# SCH_tactile_cube.net
KiCad netlist of a schematic drawn in EasyEDA
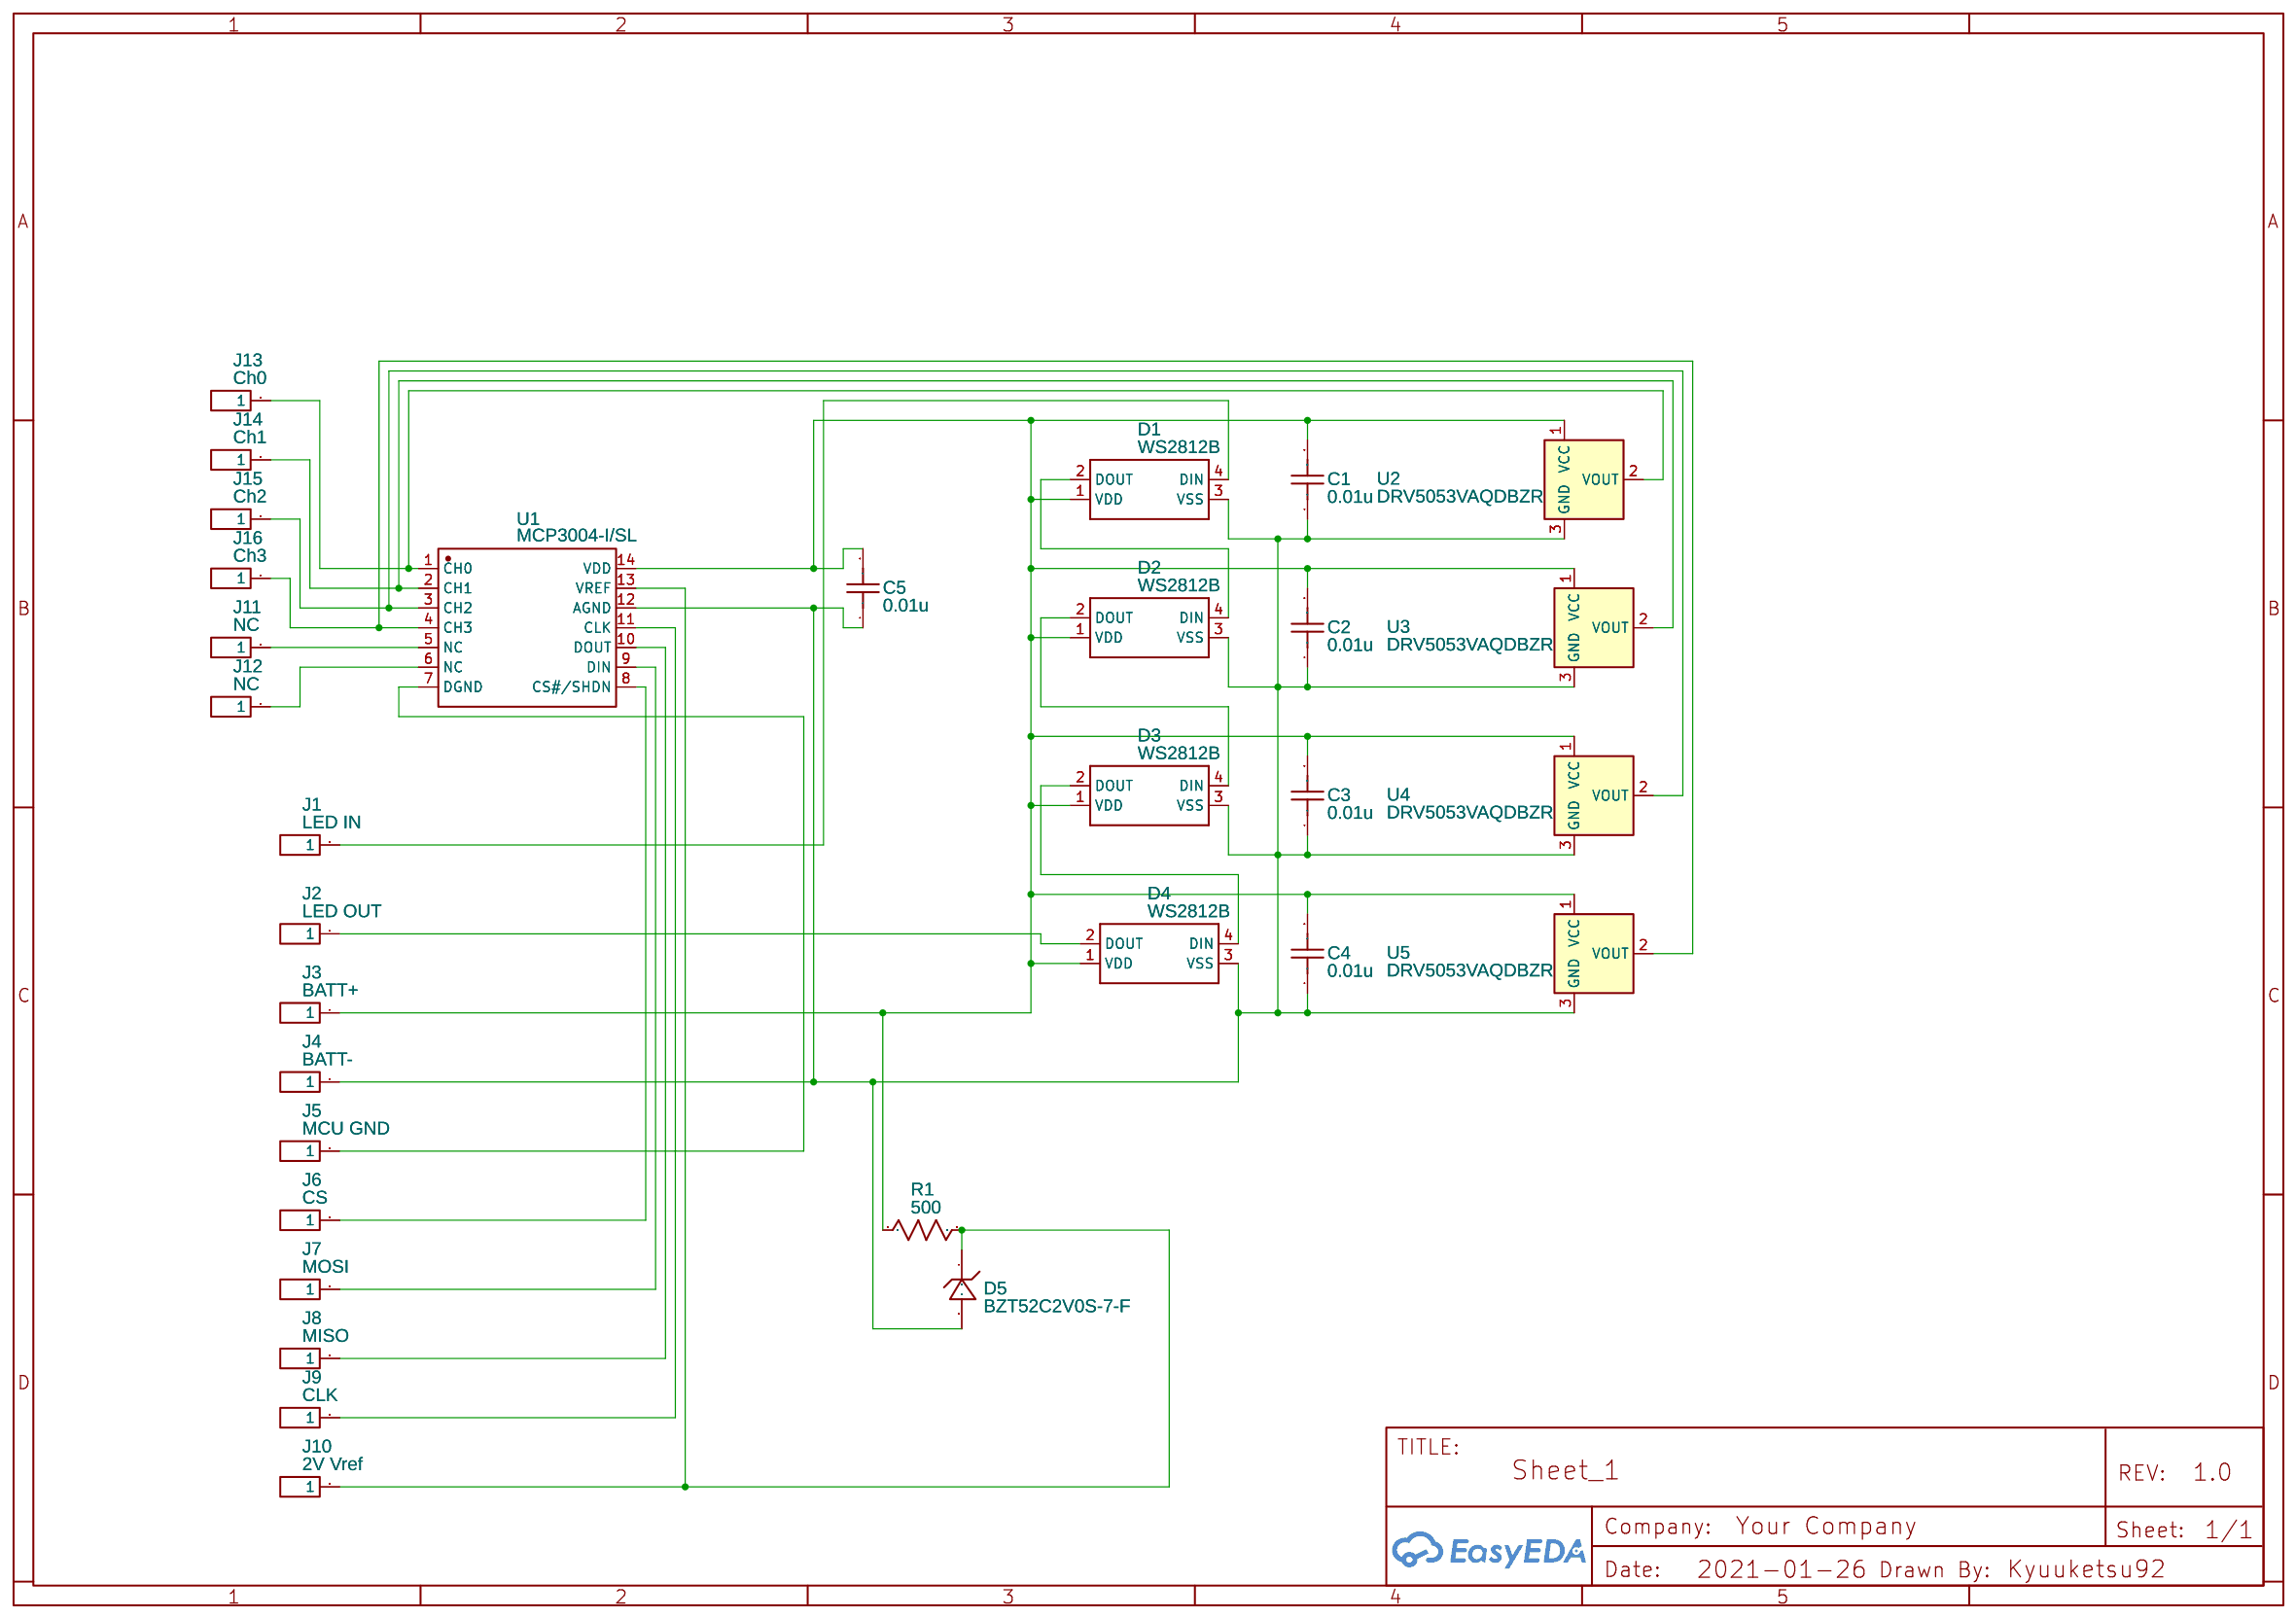
[diagram p0: schematic sheet]

(export (version "E")
  (design (tool "Eeschema 10.0.6"))
  (components
    (comp (ref "C1") (value "0.01u") (libsource (lib "") (part "C_0603_US")))
    (comp (ref "C2") (value "0.01u") (libsource (lib "") (part "C_0603_US")))
    (comp (ref "C3") (value "0.01u") (libsource (lib "") (part "C_0603_US")))
    (comp (ref "C4") (value "0.01u") (libsource (lib "") (part "C_0603_US")))
    (comp (ref "C5") (value "0.01u") (libsource (lib "") (part "C_0603_US")))
    (comp (ref "D1") (value "WS2812B") (libsource (lib "") (part "WS2812B")))
    (comp (ref "D2") (value "WS2812B") (libsource (lib "") (part "WS2812B")))
    (comp (ref "D3") (value "WS2812B") (libsource (lib "") (part "WS2812B")))
    (comp (ref "D4") (value "WS2812B") (libsource (lib "") (part "WS2812B")))
    (comp (ref "D5")
      (value "BZT52C2V0S-7-F")
      (fields (field (name "BOM_Supplier Part") "C87969"))
      (libsource (lib "") (part "BZT52C2V0S-7-F"))
    )
    (comp (ref "J1")
      (value "LED IN")
      (fields (field (name "BOM_Supplier Part") "C81276"))
      (libsource (lib "") (part "HDR-M-2.54_1x1"))
    )
    (comp (ref "J2")
      (value "LED OUT")
      (fields (field (name "BOM_Supplier Part") "C81276"))
      (libsource (lib "") (part "HDR-M-2.54_1x1"))
    )
    (comp (ref "J3")
      (value "BATT+")
      (fields (field (name "BOM_Supplier Part") "C81276"))
      (libsource (lib "") (part "HDR-M-2.54_1x1"))
    )
    (comp (ref "J4")
      (value "BATT-")
      (fields (field (name "BOM_Supplier Part") "C81276"))
      (libsource (lib "") (part "HDR-M-2.54_1x1"))
    )
    (comp (ref "J5")
      (value "MCU GND")
      (fields (field (name "BOM_Supplier Part") "C81276"))
      (libsource (lib "") (part "HDR-M-2.54_1x1"))
    )
    (comp (ref "J6")
      (value "CS")
      (fields (field (name "BOM_Supplier Part") "C81276"))
      (libsource (lib "") (part "HDR-M-2.54_1x1"))
    )
    (comp (ref "J7")
      (value "MOSI")
      (fields (field (name "BOM_Supplier Part") "C81276"))
      (libsource (lib "") (part "HDR-M-2.54_1x1"))
    )
    (comp (ref "J8")
      (value "MISO")
      (fields (field (name "BOM_Supplier Part") "C81276"))
      (libsource (lib "") (part "HDR-M-2.54_1x1"))
    )
    (comp (ref "J9")
      (value "CLK")
      (fields (field (name "BOM_Supplier Part") "C81276"))
      (libsource (lib "") (part "HDR-M-2.54_1x1"))
    )
    (comp (ref "J10")
      (value "2V Vref")
      (fields (field (name "BOM_Supplier Part") "C81276"))
      (libsource (lib "") (part "HDR-M-2.54_1x1"))
    )
    (comp (ref "J11")
      (value "NC")
      (fields (field (name "BOM_Supplier Part") "C81276"))
      (libsource (lib "") (part "HDR-M-2.54_1x1"))
    )
    (comp (ref "J12")
      (value "NC")
      (fields (field (name "BOM_Supplier Part") "C81276"))
      (libsource (lib "") (part "HDR-M-2.54_1x1"))
    )
    (comp (ref "J13")
      (value "Ch0")
      (fields (field (name "BOM_Supplier Part") "C81276"))
      (libsource (lib "") (part "HDR-M-2.54_1x1"))
    )
    (comp (ref "J14")
      (value "Ch1")
      (fields (field (name "BOM_Supplier Part") "C81276"))
      (libsource (lib "") (part "HDR-M-2.54_1x1"))
    )
    (comp (ref "J15")
      (value "Ch2")
      (fields (field (name "BOM_Supplier Part") "C81276"))
      (libsource (lib "") (part "HDR-M-2.54_1x1"))
    )
    (comp (ref "J16")
      (value "Ch3")
      (fields (field (name "BOM_Supplier Part") "C81276"))
      (libsource (lib "") (part "HDR-M-2.54_1x1"))
    )
    (comp (ref "R1") (value "500") (libsource (lib "") (part "R_0603_US")))
    (comp (ref "U1")
      (value "MCP3004-I/SL")
      (fields (field (name "BOM_Supplier Part") "C512186"))
      (libsource (lib "") (part "MCP3004-I/SL"))
    )
    (comp (ref "U2") (value "DRV5053VAQDBZR") (libsource (lib "") (part "DRV5053VAQDBZR")))
    (comp (ref "U3") (value "DRV5053VAQDBZR") (libsource (lib "") (part "DRV5053VAQDBZR")))
    (comp (ref "U4") (value "DRV5053VAQDBZR") (libsource (lib "") (part "DRV5053VAQDBZR")))
    (comp (ref "U5") (value "DRV5053VAQDBZR") (libsource (lib "") (part "DRV5053VAQDBZR")))
  )
  (nets
    (net (code "1") (name "Net-(D1-DIN)") (class "Default")
      (node (ref "D1") (pin "4") (pinfunction "DIN_4") (pintype "input"))
      (node (ref "J1") (pin "1") (pinfunction "1_1") (pintype "input"))
    )
    (net (code "2") (name "Net-(D1-DOUT)") (class "Default")
      (node (ref "D1") (pin "2") (pinfunction "DOUT_2") (pintype "output"))
      (node (ref "D2") (pin "4") (pinfunction "DIN_4") (pintype "input"))
    )
    (net (code "3") (name "Net-(D1-VDD)") (class "Default")
      (node (ref "C1") (pin "2") (pinfunction "2_2") (pintype "unspecified"))
      (node (ref "C2") (pin "2") (pinfunction "2_2") (pintype "unspecified"))
      (node (ref "C3") (pin "2") (pinfunction "2_2") (pintype "unspecified"))
      (node (ref "C4") (pin "2") (pinfunction "2_2") (pintype "unspecified"))
      (node (ref "C5") (pin "2") (pinfunction "2_2") (pintype "unspecified"))
      (node (ref "D1") (pin "1") (pinfunction "VDD_1") (pintype "passive"))
      (node (ref "D2") (pin "1") (pinfunction "VDD_1") (pintype "passive"))
      (node (ref "D3") (pin "1") (pinfunction "VDD_1") (pintype "passive"))
      (node (ref "D4") (pin "1") (pinfunction "VDD_1") (pintype "passive"))
      (node (ref "J3") (pin "1") (pinfunction "1_1") (pintype "input"))
      (node (ref "R1") (pin "1") (pinfunction "1_1") (pintype "unspecified"))
      (node (ref "U1") (pin "14") (pinfunction "VDD_14") (pintype "unspecified"))
      (node (ref "U2") (pin "1") (pinfunction "VCC_1") (pintype "bidirectional"))
      (node (ref "U3") (pin "1") (pinfunction "VCC_1") (pintype "bidirectional"))
      (node (ref "U4") (pin "1") (pinfunction "VCC_1") (pintype "bidirectional"))
      (node (ref "U5") (pin "1") (pinfunction "VCC_1") (pintype "bidirectional"))
    )
    (net (code "4") (name "Net-(D1-VSS)") (class "Default")
      (node (ref "C1") (pin "1") (pinfunction "1_1") (pintype "unspecified"))
      (node (ref "C2") (pin "1") (pinfunction "1_1") (pintype "unspecified"))
      (node (ref "C3") (pin "1") (pinfunction "1_1") (pintype "unspecified"))
      (node (ref "C4") (pin "1") (pinfunction "1_1") (pintype "unspecified"))
      (node (ref "C5") (pin "1") (pinfunction "1_1") (pintype "unspecified"))
      (node (ref "D1") (pin "3") (pinfunction "VSS_3") (pintype "passive"))
      (node (ref "D2") (pin "3") (pinfunction "VSS_3") (pintype "passive"))
      (node (ref "D3") (pin "3") (pinfunction "VSS_3") (pintype "passive"))
      (node (ref "D4") (pin "3") (pinfunction "VSS_3") (pintype "passive"))
      (node (ref "D5") (pin "2") (pinfunction "A_2") (pintype "unspecified"))
      (node (ref "J4") (pin "1") (pinfunction "1_1") (pintype "input"))
      (node (ref "U1") (pin "12") (pinfunction "AGND_12") (pintype "unspecified"))
      (node (ref "U2") (pin "3") (pinfunction "GND_3") (pintype "bidirectional"))
      (node (ref "U3") (pin "3") (pinfunction "GND_3") (pintype "bidirectional"))
      (node (ref "U4") (pin "3") (pinfunction "GND_3") (pintype "bidirectional"))
      (node (ref "U5") (pin "3") (pinfunction "GND_3") (pintype "bidirectional"))
    )
    (net (code "5") (name "Net-(D2-DOUT)") (class "Default")
      (node (ref "D2") (pin "2") (pinfunction "DOUT_2") (pintype "output"))
      (node (ref "D3") (pin "4") (pinfunction "DIN_4") (pintype "input"))
    )
    (net (code "6") (name "Net-(D3-DOUT)") (class "Default")
      (node (ref "D3") (pin "2") (pinfunction "DOUT_2") (pintype "output"))
      (node (ref "D4") (pin "4") (pinfunction "DIN_4") (pintype "input"))
    )
    (net (code "7") (name "Net-(D4-DOUT)") (class "Default")
      (node (ref "D4") (pin "2") (pinfunction "DOUT_2") (pintype "output"))
      (node (ref "J2") (pin "1") (pinfunction "1_1") (pintype "input"))
    )
    (net (code "8") (name "Net-(D5-C)") (class "Default")
      (node (ref "D5") (pin "1") (pinfunction "C_1") (pintype "unspecified"))
      (node (ref "J10") (pin "1") (pinfunction "1_1") (pintype "input"))
      (node (ref "R1") (pin "2") (pinfunction "2_2") (pintype "unspecified"))
      (node (ref "U1") (pin "13") (pinfunction "VREF_13") (pintype "unspecified"))
    )
    (net (code "9") (name "Net-(J11-Pad1)") (class "Default")
      (node (ref "J11") (pin "1") (pinfunction "1_1") (pintype "input"))
      (node (ref "U1") (pin "5") (pinfunction "NC_5") (pintype "unspecified"))
    )
    (net (code "10") (name "Net-(J12-Pad1)") (class "Default")
      (node (ref "J12") (pin "1") (pinfunction "1_1") (pintype "input"))
      (node (ref "U1") (pin "6") (pinfunction "NC_6") (pintype "unspecified"))
    )
    (net (code "11") (name "Net-(U1-CH0)") (class "Default")
      (node (ref "J13") (pin "1") (pinfunction "1_1") (pintype "input"))
      (node (ref "U1") (pin "1") (pinfunction "CH0_1") (pintype "unspecified"))
      (node (ref "U2") (pin "2") (pinfunction "VOUT_2") (pintype "output"))
    )
    (net (code "12") (name "Net-(U1-CH1)") (class "Default")
      (node (ref "J14") (pin "1") (pinfunction "1_1") (pintype "input"))
      (node (ref "U1") (pin "2") (pinfunction "CH1_2") (pintype "unspecified"))
      (node (ref "U3") (pin "2") (pinfunction "VOUT_2") (pintype "output"))
    )
    (net (code "13") (name "Net-(U1-CH2)") (class "Default")
      (node (ref "J15") (pin "1") (pinfunction "1_1") (pintype "input"))
      (node (ref "U1") (pin "3") (pinfunction "CH2_3") (pintype "unspecified"))
      (node (ref "U4") (pin "2") (pinfunction "VOUT_2") (pintype "output"))
    )
    (net (code "14") (name "Net-(U1-CH3)") (class "Default")
      (node (ref "J16") (pin "1") (pinfunction "1_1") (pintype "input"))
      (node (ref "U1") (pin "4") (pinfunction "CH3_4") (pintype "unspecified"))
      (node (ref "U5") (pin "2") (pinfunction "VOUT_2") (pintype "output"))
    )
    (net (code "15") (name "Net-(U1-CLK)") (class "Default")
      (node (ref "J9") (pin "1") (pinfunction "1_1") (pintype "input"))
      (node (ref "U1") (pin "11") (pinfunction "CLK_11") (pintype "unspecified"))
    )
    (net (code "16") (name "Net-(U1-CS#{slash}SHDN)") (class "Default")
      (node (ref "J6") (pin "1") (pinfunction "1_1") (pintype "input"))
      (node (ref "U1") (pin "8") (pinfunction "CS#/SHDN_8") (pintype "unspecified"))
    )
    (net (code "17") (name "Net-(U1-DGND)") (class "Default")
      (node (ref "J5") (pin "1") (pinfunction "1_1") (pintype "input"))
      (node (ref "U1") (pin "7") (pinfunction "DGND_7") (pintype "unspecified"))
    )
    (net (code "18") (name "Net-(U1-DIN)") (class "Default")
      (node (ref "J7") (pin "1") (pinfunction "1_1") (pintype "input"))
      (node (ref "U1") (pin "9") (pinfunction "DIN_9") (pintype "unspecified"))
    )
    (net (code "19") (name "Net-(U1-DOUT)") (class "Default")
      (node (ref "J8") (pin "1") (pinfunction "1_1") (pintype "input"))
      (node (ref "U1") (pin "10") (pinfunction "DOUT_10") (pintype "unspecified"))
    )
  )
)
